# TIVA_3.net
KiCad netlist of a schematic drawn in Altium Designer
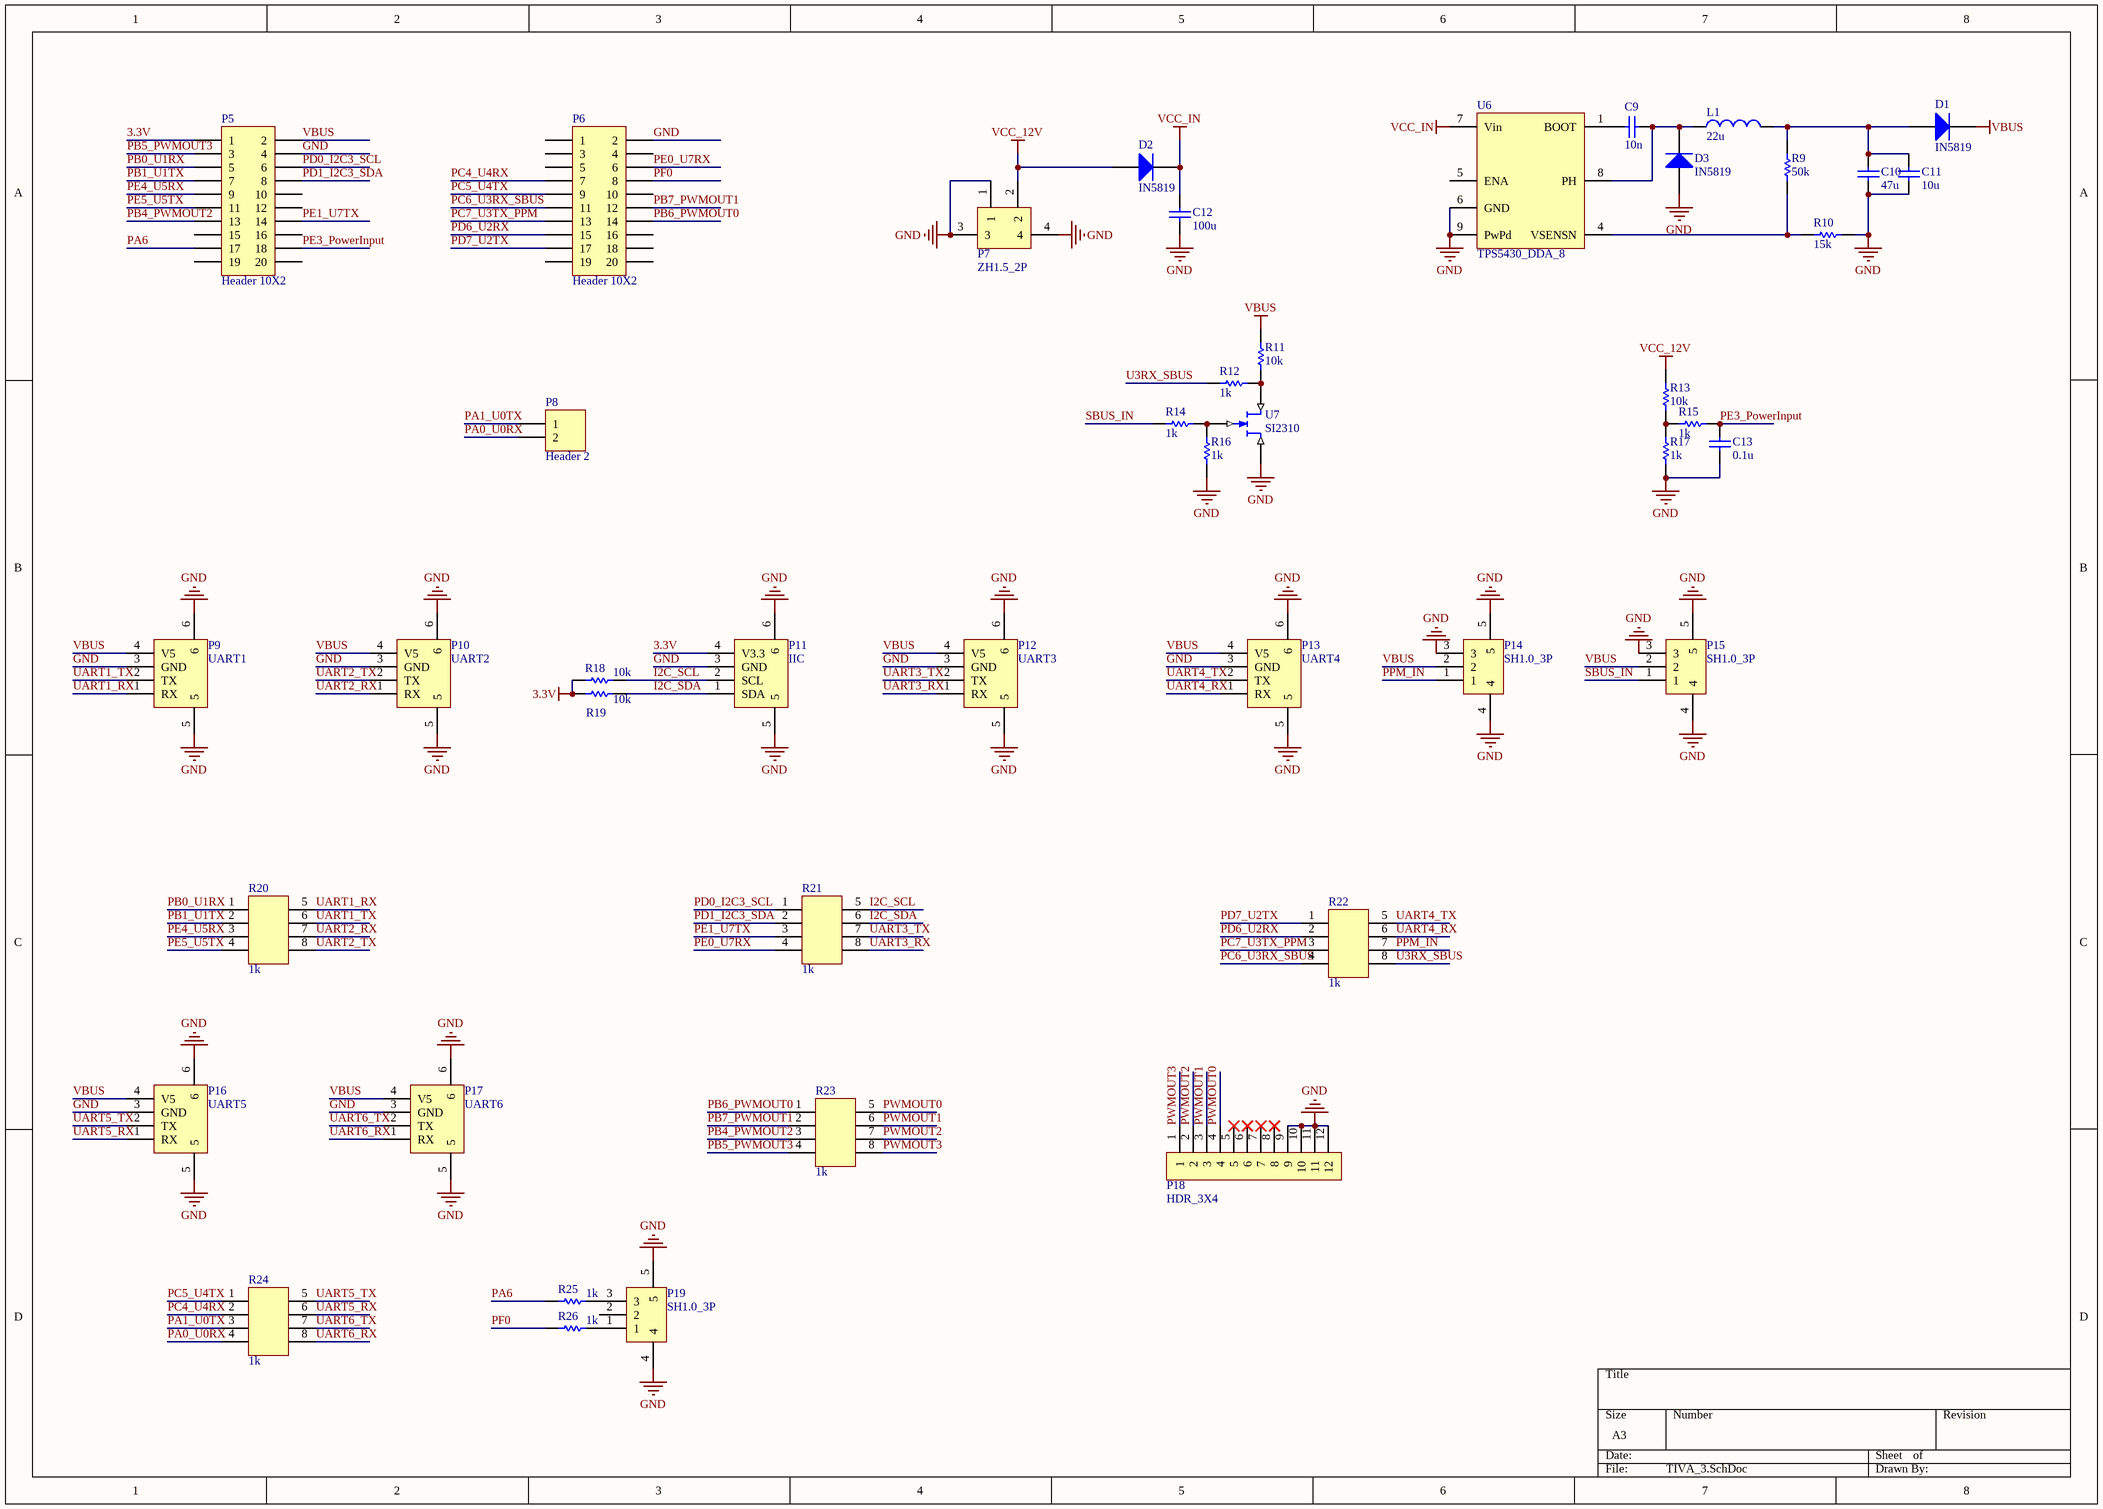
[diagram p0: TIVA_3.SchDoc]

(export (version "E")
  (design (tool "Eeschema 10.0.6"))
  (components
    (comp (ref "C9") (value "10n") (footprint "C_0805") (libsource (lib "TIVALib") (part "C_0805")))
    (comp (ref "C10") (value "47u") (footprint "C_0805") (libsource (lib "TIVALib") (part "C_0805")))
    (comp (ref "C11") (value "10u") (footprint "C_0805") (libsource (lib "TIVALib") (part "C_0805")))
    (comp (ref "C12") (value "100u") (footprint "C_1210") (libsource (lib "TIVALib") (part "C_1210")))
    (comp (ref "C13") (value "0.1u") (footprint "C_0805") (libsource (lib "TIVALib") (part "C_0805")))
    (comp (ref "D1") (value "IN5819") (footprint "SMA_SS14") (libsource (lib "TIVALib") (part "IN5819")))
    (comp (ref "D2") (value "IN5819") (footprint "SMA_SS14") (libsource (lib "TIVALib") (part "IN5819")))
    (comp (ref "D3") (value "IN5819") (footprint "SMA_SS14") (libsource (lib "TIVALib") (part "IN5819")))
    (comp (ref "L1") (value "22u") (footprint "L_06030") (libsource (lib "TIVALib") (part "L_06030")))
    (comp (ref "P5")
      (value "Header 10X2")
      (footprint "HDR2X10")
      (description "Header, 10-Pin, Dual row")
      (fields (field (name "PUBLISHER") "Altium Limited"))
      (libsource (lib "TIVALib") (part "Header 10X2"))
    )
    (comp (ref "P6")
      (value "Header 10X2")
      (footprint "HDR2X10")
      (description "Header, 10-Pin, Dual row")
      (fields (field (name "PUBLISHER") "Altium Limited"))
      (libsource (lib "TIVALib") (part "Header 10X2"))
    )
    (comp (ref "P7") (value "ZH1.5_2P") (footprint "ZH1.5_2P") (libsource (lib "TIVALib") (part "ZH1.5_2P")))
    (comp (ref "P8")
      (value "Header 2")
      (footprint "HDR1X2")
      (description "Header, 2-Pin")
      (fields (field (name "PUBLISHER") "Altium Limited"))
      (libsource (lib "TIVALib") (part "Header 2"))
    )
    (comp (ref "P9") (value "UART1") (footprint "SH1.0_4p") (libsource (lib "TIVALib") (part "UART")))
    (comp (ref "P10") (value "UART2") (footprint "SH1.0_4p") (libsource (lib "TIVALib") (part "UART")))
    (comp (ref "P11") (value "IIC") (footprint "SH1.0_4p") (libsource (lib "TIVALib") (part "IIC")))
    (comp (ref "P12") (value "UART3") (footprint "SH1.0_4p") (libsource (lib "TIVALib") (part "UART")))
    (comp (ref "P13") (value "UART4") (footprint "SH1.0_4p") (libsource (lib "TIVALib") (part "UART")))
    (comp (ref "P14") (value "SH1.0_3P") (footprint "SH1.0_3P") (libsource (lib "TIVALib") (part "SH1.0_3P")))
    (comp (ref "P15") (value "SH1.0_3P") (footprint "SH1.0_3P") (libsource (lib "TIVALib") (part "SH1.0_3P")))
    (comp (ref "P16") (value "UART5") (footprint "SH1.0_4p") (libsource (lib "TIVALib") (part "UART")))
    (comp (ref "P17") (value "UART6") (footprint "SH1.0_4p") (libsource (lib "TIVALib") (part "UART")))
    (comp (ref "P18") (value "HDR_3X4") (footprint "HDR3X4") (libsource (lib "TIVALib") (part "HDR_3X4")))
    (comp (ref "P19") (value "SH1.0_3P") (footprint "SH1.0_3P") (libsource (lib "TIVALib") (part "SH1.0_3P")))
    (comp (ref "R9") (value "50k") (footprint "R_0805") (libsource (lib "TIVALib") (part "R_0805")))
    (comp (ref "R10") (value "15k") (footprint "R_0805") (libsource (lib "TIVALib") (part "R_0805")))
    (comp (ref "R11") (value "10k") (footprint "R_0805") (libsource (lib "TIVALib") (part "R_0805")))
    (comp (ref "R12") (value "1k") (footprint "R_0805") (libsource (lib "TIVALib") (part "R_0805")))
    (comp (ref "R13") (value "10k") (footprint "R_0805") (libsource (lib "TIVALib") (part "R_0805")))
    (comp (ref "R14") (value "1k") (footprint "R_0805") (libsource (lib "TIVALib") (part "R_0805")))
    (comp (ref "R15") (value "1k") (footprint "R_0805") (libsource (lib "TIVALib") (part "R_0805")))
    (comp (ref "R16") (value "1k") (footprint "R_0805") (libsource (lib "TIVALib") (part "R_0805")))
    (comp (ref "R17") (value "1k") (footprint "R_0805") (libsource (lib "TIVALib") (part "R_0805")))
    (comp (ref "R18") (value "10k") (footprint "R_0805") (libsource (lib "TIVALib") (part "R_0805")))
    (comp (ref "R19") (value "10k") (footprint "R_0805") (libsource (lib "TIVALib") (part "R_0805")))
    (comp (ref "R20") (value "1k") (footprint "HDR_R_4") (libsource (lib "TIVALib") (part "R_4")))
    (comp (ref "R21") (value "1k") (footprint "HDR_R_4") (libsource (lib "TIVALib") (part "R_4")))
    (comp (ref "R22") (value "1k") (footprint "HDR_R_4") (libsource (lib "TIVALib") (part "R_4")))
    (comp (ref "R23") (value "1k") (footprint "HDR_R_4") (libsource (lib "TIVALib") (part "R_4")))
    (comp (ref "R24") (value "1k") (footprint "HDR_R_4") (libsource (lib "TIVALib") (part "R_4")))
    (comp (ref "R25") (value "1k") (footprint "R_0805") (libsource (lib "TIVALib") (part "R_0805")))
    (comp (ref "R26") (value "1k") (footprint "R_0805") (libsource (lib "TIVALib") (part "R_0805")))
    (comp (ref "U6")
      (value "TPS5430_DDA_8")
      (footprint "DDA8_3P1X2P4")
      (description "Imported")
      (fields
        (field (name "MANUFACTURER_PART_NUMBER") "tps5430_dda_8")
        (field (name "GENERIC_PART_NUMBER") "TPS5430")
      )
      (libsource (lib "TIVALib") (part "TPS5430_DDA_8"))
    )
    (comp (ref "U7") (value "SI2310") (footprint "SOT_23") (libsource (lib "TIVALib") (part "SI2310_2")))
  )
  (nets
    (net (code "1") (name "/I2C_SCL") (class "Default")
      (node (ref "P11") (pin "2") (pinfunction "SCL_2") (pintype "passive"))
      (node (ref "R18") (pin "1") (pinfunction "1_1") (pintype "passive"))
      (node (ref "R21") (pin "5") (pintype "passive"))
    )
    (net (code "2") (name "/I2C_SDA") (class "Default")
      (node (ref "P11") (pin "1") (pinfunction "SDA_1") (pintype "passive"))
      (node (ref "R19") (pin "1") (pinfunction "1_1") (pintype "passive"))
      (node (ref "R21") (pin "6") (pintype "passive"))
    )
    (net (code "3") (name "/PA0_U0RX") (class "Default")
      (node (ref "P8") (pin "2") (pinfunction "2_2") (pintype "passive"))
      (node (ref "R24") (pin "4") (pintype "passive"))
    )
    (net (code "4") (name "/PA1_U0TX") (class "Default")
      (node (ref "P8") (pin "1") (pinfunction "1_1") (pintype "passive"))
      (node (ref "R24") (pin "3") (pintype "passive"))
    )
    (net (code "5") (name "/PA6") (class "Default")
      (node (ref "P5") (pin "17") (pinfunction "17_17") (pintype "passive"))
      (node (ref "R25") (pin "1") (pinfunction "1_1") (pintype "passive"))
    )
    (net (code "6") (name "/PB0_U1RX") (class "Default")
      (node (ref "P5") (pin "5") (pinfunction "5_5") (pintype "passive"))
      (node (ref "R20") (pin "1") (pintype "passive"))
    )
    (net (code "7") (name "/PB1_U1TX") (class "Default")
      (node (ref "P5") (pin "7") (pinfunction "7_7") (pintype "passive"))
      (node (ref "R20") (pin "2") (pintype "passive"))
    )
    (net (code "8") (name "/PB4_PWMOUT2") (class "Default")
      (node (ref "P5") (pin "13") (pinfunction "13_13") (pintype "passive"))
      (node (ref "R23") (pin "3") (pintype "passive"))
    )
    (net (code "9") (name "/PB5_PWMOUT3") (class "Default")
      (node (ref "P5") (pin "3") (pinfunction "3_3") (pintype "passive"))
      (node (ref "R23") (pin "4") (pintype "passive"))
    )
    (net (code "10") (name "/PB6_PWMOUT0") (class "Default")
      (node (ref "P6") (pin "14") (pinfunction "14_14") (pintype "passive"))
      (node (ref "R23") (pin "1") (pintype "passive"))
    )
    (net (code "11") (name "/PB7_PWMOUT1") (class "Default")
      (node (ref "P6") (pin "12") (pinfunction "12_12") (pintype "passive"))
      (node (ref "R23") (pin "2") (pintype "passive"))
    )
    (net (code "12") (name "/PC4_U4RX") (class "Default")
      (node (ref "P6") (pin "7") (pinfunction "7_7") (pintype "passive"))
      (node (ref "R24") (pin "2") (pintype "passive"))
    )
    (net (code "13") (name "/PC5_U4TX") (class "Default")
      (node (ref "P6") (pin "9") (pinfunction "9_9") (pintype "passive"))
      (node (ref "R24") (pin "1") (pintype "passive"))
    )
    (net (code "14") (name "/PC6_U3RX_SBUS") (class "Default")
      (node (ref "P6") (pin "11") (pinfunction "11_11") (pintype "passive"))
      (node (ref "R22") (pin "4") (pintype "passive"))
    )
    (net (code "15") (name "/PC7_U3TX_PPM") (class "Default")
      (node (ref "P6") (pin "13") (pinfunction "13_13") (pintype "passive"))
      (node (ref "R22") (pin "3") (pintype "passive"))
    )
    (net (code "16") (name "/PD0_I2C3_SCL") (class "Default")
      (node (ref "P5") (pin "6") (pinfunction "6_6") (pintype "passive"))
      (node (ref "R21") (pin "1") (pintype "passive"))
    )
    (net (code "17") (name "/PD1_I2C3_SDA") (class "Default")
      (node (ref "P5") (pin "8") (pinfunction "8_8") (pintype "passive"))
      (node (ref "R21") (pin "2") (pintype "passive"))
    )
    (net (code "18") (name "/PD6_U2RX") (class "Default")
      (node (ref "P6") (pin "15") (pinfunction "15_15") (pintype "passive"))
      (node (ref "R22") (pin "2") (pintype "passive"))
    )
    (net (code "19") (name "/PD7_U2TX") (class "Default")
      (node (ref "P6") (pin "17") (pinfunction "17_17") (pintype "passive"))
      (node (ref "R22") (pin "1") (pintype "passive"))
    )
    (net (code "20") (name "/PE0_U7RX") (class "Default")
      (node (ref "P6") (pin "6") (pinfunction "6_6") (pintype "passive"))
      (node (ref "R21") (pin "4") (pintype "passive"))
    )
    (net (code "21") (name "/PE1_U7TX") (class "Default")
      (node (ref "P5") (pin "14") (pinfunction "14_14") (pintype "passive"))
      (node (ref "R21") (pin "3") (pintype "passive"))
    )
    (net (code "22") (name "/PE3_PowerInput") (class "Default")
      (node (ref "C13") (pin "2") (pinfunction "2_2") (pintype "passive"))
      (node (ref "P5") (pin "18") (pinfunction "18_18") (pintype "passive"))
      (node (ref "R15") (pin "1") (pinfunction "1_1") (pintype "passive"))
    )
    (net (code "23") (name "/PE4_U5RX") (class "Default")
      (node (ref "P5") (pin "9") (pinfunction "9_9") (pintype "passive"))
      (node (ref "R20") (pin "3") (pintype "passive"))
    )
    (net (code "24") (name "/PE5_U5TX") (class "Default")
      (node (ref "P5") (pin "11") (pinfunction "11_11") (pintype "passive"))
      (node (ref "R20") (pin "4") (pintype "passive"))
    )
    (net (code "25") (name "/PF0") (class "Default")
      (node (ref "P6") (pin "8") (pinfunction "8_8") (pintype "passive"))
      (node (ref "R26") (pin "1") (pinfunction "1_1") (pintype "passive"))
    )
    (net (code "26") (name "/PPM_IN") (class "Default")
      (node (ref "P14") (pin "1") (pinfunction "1_1") (pintype "passive"))
      (node (ref "R22") (pin "7") (pintype "passive"))
    )
    (net (code "27") (name "/PWMOUT0") (class "Default")
      (node (ref "P18") (pin "4") (pinfunction "4_4") (pintype "passive"))
      (node (ref "R23") (pin "5") (pintype "passive"))
    )
    (net (code "28") (name "/PWMOUT1") (class "Default")
      (node (ref "P18") (pin "3") (pinfunction "3_3") (pintype "passive"))
      (node (ref "R23") (pin "6") (pintype "passive"))
    )
    (net (code "29") (name "/PWMOUT2") (class "Default")
      (node (ref "P18") (pin "2") (pinfunction "2_2") (pintype "passive"))
      (node (ref "R23") (pin "7") (pintype "passive"))
    )
    (net (code "30") (name "/PWMOUT3") (class "Default")
      (node (ref "P18") (pin "1") (pinfunction "1_1") (pintype "passive"))
      (node (ref "R23") (pin "8") (pintype "passive"))
    )
    (net (code "31") (name "/SBUS_IN") (class "Default")
      (node (ref "P15") (pin "1") (pinfunction "1_1") (pintype "passive"))
      (node (ref "R14") (pin "2") (pinfunction "2_2") (pintype "passive"))
    )
    (net (code "32") (name "/U3RX_SBUS") (class "Default")
      (node (ref "R12") (pin "2") (pinfunction "2_2") (pintype "passive"))
      (node (ref "R22") (pin "8") (pintype "passive"))
    )
    (net (code "33") (name "/UART1_RX") (class "Default")
      (node (ref "P9") (pin "1") (pinfunction "RX_1") (pintype "passive"))
      (node (ref "R20") (pin "5") (pintype "passive"))
    )
    (net (code "34") (name "/UART1_TX") (class "Default")
      (node (ref "P9") (pin "2") (pinfunction "TX_2") (pintype "passive"))
      (node (ref "R20") (pin "6") (pintype "passive"))
    )
    (net (code "35") (name "/UART2_RX") (class "Default")
      (node (ref "P10") (pin "1") (pinfunction "RX_1") (pintype "passive"))
      (node (ref "R20") (pin "7") (pintype "passive"))
    )
    (net (code "36") (name "/UART2_TX") (class "Default")
      (node (ref "P10") (pin "2") (pinfunction "TX_2") (pintype "passive"))
      (node (ref "R20") (pin "8") (pintype "passive"))
    )
    (net (code "37") (name "/UART3_RX") (class "Default")
      (node (ref "P12") (pin "1") (pinfunction "RX_1") (pintype "passive"))
      (node (ref "R21") (pin "8") (pintype "passive"))
    )
    (net (code "38") (name "/UART3_TX") (class "Default")
      (node (ref "P12") (pin "2") (pinfunction "TX_2") (pintype "passive"))
      (node (ref "R21") (pin "7") (pintype "passive"))
    )
    (net (code "39") (name "/UART4_RX") (class "Default")
      (node (ref "P13") (pin "1") (pinfunction "RX_1") (pintype "passive"))
      (node (ref "R22") (pin "6") (pintype "passive"))
    )
    (net (code "40") (name "/UART4_TX") (class "Default")
      (node (ref "P13") (pin "2") (pinfunction "TX_2") (pintype "passive"))
      (node (ref "R22") (pin "5") (pintype "passive"))
    )
    (net (code "41") (name "/UART5_RX") (class "Default")
      (node (ref "P16") (pin "1") (pinfunction "RX_1") (pintype "passive"))
      (node (ref "R24") (pin "6") (pintype "passive"))
    )
    (net (code "42") (name "/UART5_TX") (class "Default")
      (node (ref "P16") (pin "2") (pinfunction "TX_2") (pintype "passive"))
      (node (ref "R24") (pin "5") (pintype "passive"))
    )
    (net (code "43") (name "/UART6_RX") (class "Default")
      (node (ref "P17") (pin "1") (pinfunction "RX_1") (pintype "passive"))
      (node (ref "R24") (pin "8") (pintype "passive"))
    )
    (net (code "44") (name "/UART6_TX") (class "Default")
      (node (ref "P17") (pin "2") (pinfunction "TX_2") (pintype "passive"))
      (node (ref "R24") (pin "7") (pintype "passive"))
    )
    (net (code "45") (name "3.3V") (class "Default")
      (node (ref "P11") (pin "4") (pinfunction "V3.3_4") (pintype "passive"))
      (node (ref "P5") (pin "1") (pinfunction "1_1") (pintype "passive"))
      (node (ref "R18") (pin "2") (pinfunction "2_2") (pintype "passive"))
      (node (ref "R19") (pin "2") (pinfunction "2_2") (pintype "passive"))
    )
    (net (code "46") (name "GND") (class "Default")
      (node (ref "C10") (pin "1") (pinfunction "1_1") (pintype "passive"))
      (node (ref "C11") (pin "1") (pinfunction "1_1") (pintype "passive"))
      (node (ref "C12") (pin "1") (pinfunction "1_1") (pintype "passive"))
      (node (ref "C13") (pin "1") (pinfunction "1_1") (pintype "passive"))
      (node (ref "D3") (pin "1") (pinfunction "A_1") (pintype "passive"))
      (node (ref "P10") (pin "3") (pinfunction "GND_3") (pintype "passive"))
      (node (ref "P10") (pin "5") (pinfunction "5_5") (pintype "passive"))
      (node (ref "P10") (pin "6") (pinfunction "6_6") (pintype "passive"))
      (node (ref "P11") (pin "3") (pinfunction "GND_3") (pintype "passive"))
      (node (ref "P11") (pin "5") (pinfunction "5_5") (pintype "passive"))
      (node (ref "P11") (pin "6") (pinfunction "6_6") (pintype "passive"))
      (node (ref "P12") (pin "3") (pinfunction "GND_3") (pintype "passive"))
      (node (ref "P12") (pin "5") (pinfunction "5_5") (pintype "passive"))
      (node (ref "P12") (pin "6") (pinfunction "6_6") (pintype "passive"))
      (node (ref "P13") (pin "3") (pinfunction "GND_3") (pintype "passive"))
      (node (ref "P13") (pin "5") (pinfunction "5_5") (pintype "passive"))
      (node (ref "P13") (pin "6") (pinfunction "6_6") (pintype "passive"))
      (node (ref "P14") (pin "3") (pinfunction "3_3") (pintype "passive"))
      (node (ref "P14") (pin "4") (pinfunction "4_4") (pintype "passive"))
      (node (ref "P14") (pin "5") (pinfunction "5_5") (pintype "passive"))
      (node (ref "P15") (pin "3") (pinfunction "3_3") (pintype "passive"))
      (node (ref "P15") (pin "4") (pinfunction "4_4") (pintype "passive"))
      (node (ref "P15") (pin "5") (pinfunction "5_5") (pintype "passive"))
      (node (ref "P16") (pin "3") (pinfunction "GND_3") (pintype "passive"))
      (node (ref "P16") (pin "5") (pinfunction "5_5") (pintype "passive"))
      (node (ref "P16") (pin "6") (pinfunction "6_6") (pintype "passive"))
      (node (ref "P17") (pin "3") (pinfunction "GND_3") (pintype "passive"))
      (node (ref "P17") (pin "5") (pinfunction "5_5") (pintype "passive"))
      (node (ref "P17") (pin "6") (pinfunction "6_6") (pintype "passive"))
      (node (ref "P18") (pin "10") (pinfunction "10_10") (pintype "passive"))
      (node (ref "P18") (pin "11") (pinfunction "11_11") (pintype "passive"))
      (node (ref "P18") (pin "12") (pinfunction "12_12") (pintype "passive"))
      (node (ref "P18") (pin "9") (pinfunction "9_9") (pintype "passive"))
      (node (ref "P19") (pin "4") (pinfunction "4_4") (pintype "passive"))
      (node (ref "P19") (pin "5") (pinfunction "5_5") (pintype "passive"))
      (node (ref "P5") (pin "4") (pinfunction "4_4") (pintype "passive"))
      (node (ref "P6") (pin "2") (pinfunction "2_2") (pintype "passive"))
      (node (ref "P7") (pin "1") (pinfunction "1_1") (pintype "passive"))
      (node (ref "P7") (pin "3") (pinfunction "3_3") (pintype "passive"))
      (node (ref "P7") (pin "4") (pinfunction "4_4") (pintype "passive"))
      (node (ref "P9") (pin "3") (pinfunction "GND_3") (pintype "passive"))
      (node (ref "P9") (pin "5") (pinfunction "5_5") (pintype "passive"))
      (node (ref "P9") (pin "6") (pinfunction "6_6") (pintype "passive"))
      (node (ref "R10") (pin "1") (pinfunction "1_1") (pintype "passive"))
      (node (ref "R16") (pin "2") (pinfunction "2_2") (pintype "passive"))
      (node (ref "R17") (pin "1") (pinfunction "1_1") (pintype "passive"))
      (node (ref "U6") (pin "6") (pinfunction "GND_6") (pintype "passive"))
      (node (ref "U6") (pin "9") (pinfunction "PwPd_9") (pintype "passive"))
      (node (ref "U7") (pin "2") (pinfunction "S_2") (pintype "input"))
    )
    (net (code "47") (name "Net-(D1-A)") (class "Default")
      (node (ref "C10") (pin "2") (pinfunction "2_2") (pintype "passive"))
      (node (ref "C11") (pin "2") (pinfunction "2_2") (pintype "passive"))
      (node (ref "D1") (pin "1") (pinfunction "A_1") (pintype "passive"))
      (node (ref "L1") (pin "2") (pinfunction "2_2") (pintype "passive"))
      (node (ref "R9") (pin "2") (pinfunction "2_2") (pintype "passive"))
    )
    (net (code "48") (name "Net-(D3-K)") (class "Default")
      (node (ref "C9") (pin "1") (pinfunction "1_1") (pintype "passive"))
      (node (ref "D3") (pin "2") (pinfunction "K_2") (pintype "passive"))
      (node (ref "L1") (pin "1") (pinfunction "1_1") (pintype "passive"))
      (node (ref "U6") (pin "8") (pinfunction "PH_8") (pintype "passive"))
    )
    (net (code "49") (name "Net-(P19-Pad1)") (class "Default")
      (node (ref "P19") (pin "1") (pinfunction "1_1") (pintype "passive"))
      (node (ref "R26") (pin "2") (pinfunction "2_2") (pintype "passive"))
    )
    (net (code "50") (name "Net-(P19-Pad3)") (class "Default")
      (node (ref "P19") (pin "3") (pinfunction "3_3") (pintype "passive"))
      (node (ref "R25") (pin "2") (pinfunction "2_2") (pintype "passive"))
    )
    (net (code "51") (name "Net-(R13-Pad1)") (class "Default")
      (node (ref "R13") (pin "1") (pinfunction "1_1") (pintype "passive"))
      (node (ref "R15") (pin "2") (pinfunction "2_2") (pintype "passive"))
      (node (ref "R17") (pin "2") (pinfunction "2_2") (pintype "passive"))
    )
    (net (code "52") (name "Net-(U6-BOOT)") (class "Default")
      (node (ref "C9") (pin "2") (pinfunction "2_2") (pintype "passive"))
      (node (ref "U6") (pin "1") (pinfunction "BOOT_1") (pintype "passive"))
    )
    (net (code "53") (name "Net-(U6-VSENSN)") (class "Default")
      (node (ref "R10") (pin "2") (pinfunction "2_2") (pintype "passive"))
      (node (ref "R9") (pin "1") (pinfunction "1_1") (pintype "passive"))
      (node (ref "U6") (pin "4") (pinfunction "VSENSN_4") (pintype "passive"))
    )
    (net (code "54") (name "Net-(U7-D)") (class "Default")
      (node (ref "R11") (pin "1") (pinfunction "1_1") (pintype "passive"))
      (node (ref "R12") (pin "1") (pinfunction "1_1") (pintype "passive"))
      (node (ref "U7") (pin "3") (pinfunction "D_3") (pintype "input"))
    )
    (net (code "55") (name "Net-(U7-G)") (class "Default")
      (node (ref "R14") (pin "1") (pinfunction "1_1") (pintype "passive"))
      (node (ref "R16") (pin "1") (pinfunction "1_1") (pintype "passive"))
      (node (ref "U7") (pin "1") (pinfunction "G_1") (pintype "input"))
    )
    (net (code "56") (name "VBUS") (class "Default")
      (node (ref "D1") (pin "2") (pinfunction "K_2") (pintype "passive"))
      (node (ref "P10") (pin "4") (pinfunction "V5_4") (pintype "passive"))
      (node (ref "P12") (pin "4") (pinfunction "V5_4") (pintype "passive"))
      (node (ref "P13") (pin "4") (pinfunction "V5_4") (pintype "passive"))
      (node (ref "P14") (pin "2") (pinfunction "2_2") (pintype "passive"))
      (node (ref "P15") (pin "2") (pinfunction "2_2") (pintype "passive"))
      (node (ref "P16") (pin "4") (pinfunction "V5_4") (pintype "passive"))
      (node (ref "P17") (pin "4") (pinfunction "V5_4") (pintype "passive"))
      (node (ref "P5") (pin "2") (pinfunction "2_2") (pintype "passive"))
      (node (ref "P9") (pin "4") (pinfunction "V5_4") (pintype "passive"))
      (node (ref "R11") (pin "2") (pinfunction "2_2") (pintype "passive"))
    )
    (net (code "57") (name "VCC_12V") (class "Default")
      (node (ref "D2") (pin "1") (pinfunction "A_1") (pintype "passive"))
      (node (ref "P7") (pin "2") (pinfunction "2_2") (pintype "passive"))
      (node (ref "R13") (pin "2") (pinfunction "2_2") (pintype "passive"))
    )
    (net (code "58") (name "VCC_IN") (class "Default")
      (node (ref "C12") (pin "2") (pinfunction "2_2") (pintype "passive"))
      (node (ref "D2") (pin "2") (pinfunction "K_2") (pintype "passive"))
      (node (ref "U6") (pin "7") (pinfunction "Vin_7") (pintype "passive"))
    )
    (net (code "59") (name "unconnected-(P5-Pad10)") (class "Default")
      (node (ref "P5") (pin "10") (pinfunction "10_10") (pintype "passive"))
    )
    (net (code "60") (name "unconnected-(P5-Pad12)") (class "Default")
      (node (ref "P5") (pin "12") (pinfunction "12_12") (pintype "passive"))
    )
    (net (code "61") (name "unconnected-(P5-Pad15)") (class "Default")
      (node (ref "P5") (pin "15") (pinfunction "15_15") (pintype "passive"))
    )
    (net (code "62") (name "unconnected-(P5-Pad16)") (class "Default")
      (node (ref "P5") (pin "16") (pinfunction "16_16") (pintype "passive"))
    )
    (net (code "63") (name "unconnected-(P5-Pad19)") (class "Default")
      (node (ref "P5") (pin "19") (pinfunction "19_19") (pintype "passive"))
    )
    (net (code "64") (name "unconnected-(P5-Pad20)") (class "Default")
      (node (ref "P5") (pin "20") (pinfunction "20_20") (pintype "passive"))
    )
    (net (code "65") (name "unconnected-(P6-Pad1)") (class "Default")
      (node (ref "P6") (pin "1") (pinfunction "1_1") (pintype "passive"))
    )
    (net (code "66") (name "unconnected-(P6-Pad3)") (class "Default")
      (node (ref "P6") (pin "3") (pinfunction "3_3") (pintype "passive"))
    )
    (net (code "67") (name "unconnected-(P6-Pad4)") (class "Default")
      (node (ref "P6") (pin "4") (pinfunction "4_4") (pintype "passive"))
    )
    (net (code "68") (name "unconnected-(P6-Pad5)") (class "Default")
      (node (ref "P6") (pin "5") (pinfunction "5_5") (pintype "passive"))
    )
    (net (code "69") (name "unconnected-(P6-Pad10)") (class "Default")
      (node (ref "P6") (pin "10") (pinfunction "10_10") (pintype "passive"))
    )
    (net (code "70") (name "unconnected-(P6-Pad16)") (class "Default")
      (node (ref "P6") (pin "16") (pinfunction "16_16") (pintype "passive"))
    )
    (net (code "71") (name "unconnected-(P6-Pad18)") (class "Default")
      (node (ref "P6") (pin "18") (pinfunction "18_18") (pintype "passive"))
    )
    (net (code "72") (name "unconnected-(P6-Pad19)") (class "Default")
      (node (ref "P6") (pin "19") (pinfunction "19_19") (pintype "passive"))
    )
    (net (code "73") (name "unconnected-(P6-Pad20)") (class "Default")
      (node (ref "P6") (pin "20") (pinfunction "20_20") (pintype "passive"))
    )
    (net (code "74") (name "unconnected-(P18-Pad5)") (class "Default")
      (node (ref "P18") (pin "5") (pinfunction "5_5") (pintype "passive+no_connect"))
    )
    (net (code "75") (name "unconnected-(P18-Pad6)") (class "Default")
      (node (ref "P18") (pin "6") (pinfunction "6_6") (pintype "passive+no_connect"))
    )
    (net (code "76") (name "unconnected-(P18-Pad7)") (class "Default")
      (node (ref "P18") (pin "7") (pinfunction "7_7") (pintype "passive+no_connect"))
    )
    (net (code "77") (name "unconnected-(P18-Pad8)") (class "Default")
      (node (ref "P18") (pin "8") (pinfunction "8_8") (pintype "passive+no_connect"))
    )
    (net (code "78") (name "unconnected-(P19-Pad2)") (class "Default")
      (node (ref "P19") (pin "2") (pinfunction "2_2") (pintype "passive"))
    )
    (net (code "79") (name "unconnected-(U6-ENA-Pad5)") (class "Default")
      (node (ref "U6") (pin "5") (pinfunction "ENA_5") (pintype "passive"))
    )
  )
)
